# Sheet1.net
KiCad netlist of a schematic drawn in Altium Designer
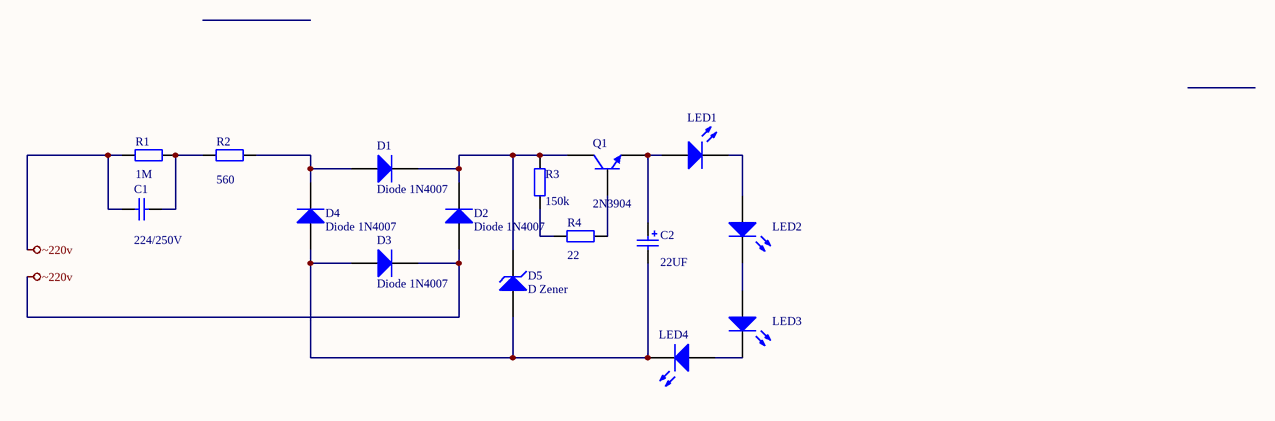
[diagram p0: Sheet1.SchDoc]

(export (version "E")
  (design (tool "Eeschema 10.0.6"))
  (components
    (comp (ref "C1")
      (value "224/250V")
      (footprint "RAD-0.3")
      (description "Capacitor")
      (fields (field (name "PUBLISHER") "Altium Limited"))
      (libsource (lib "Miscellaneous Devices") (part "Cap"))
    )
    (comp (ref "C2")
      (value "22UF")
      (footprint "POLAR0.8")
      (description "Polarized Capacitor (Axial)")
      (fields (field (name "PUBLISHER") "Altium Limited"))
      (libsource (lib "Miscellaneous Devices") (part "Cap Pol2"))
    )
    (comp (ref "D1")
      (value "Diode 1N4007")
      (footprint "DO-41")
      (description "1 Amp General Purpose Rectifier")
      (fields (field (name "PUBLISHER") "Altium Limited"))
      (libsource (lib "Miscellaneous Devices") (part "Diode 1N4007"))
    )
    (comp (ref "D2")
      (value "Diode 1N4007")
      (footprint "DO-41")
      (description "1 Amp General Purpose Rectifier")
      (fields (field (name "PUBLISHER") "Altium Limited"))
      (libsource (lib "Miscellaneous Devices") (part "Diode 1N4007"))
    )
    (comp (ref "D3")
      (value "Diode 1N4007")
      (footprint "DO-41")
      (description "1 Amp General Purpose Rectifier")
      (fields (field (name "PUBLISHER") "Altium Limited"))
      (libsource (lib "Miscellaneous Devices") (part "Diode 1N4007"))
    )
    (comp (ref "D4")
      (value "Diode 1N4007")
      (footprint "DO-41")
      (description "1 Amp General Purpose Rectifier")
      (fields (field (name "PUBLISHER") "Altium Limited"))
      (libsource (lib "Miscellaneous Devices") (part "Diode 1N4007"))
    )
    (comp (ref "D5")
      (value "D Zener")
      (footprint "DIODE-0.7")
      (description "Zener Diode")
      (fields (field (name "PUBLISHER") "Altium Limited"))
      (libsource (lib "Miscellaneous Devices") (part "D Zener"))
    )
    (comp (ref "LED1")
      (value "~")
      (footprint "LED-0")
      (description "Typical INFRARED GaAs LED")
      (fields (field (name "PUBLISHER") "Altium Limited"))
      (libsource (lib "Miscellaneous Devices") (part "LED0"))
    )
    (comp (ref "LED2")
      (value "~")
      (footprint "LED-0")
      (description "Typical INFRARED GaAs LED")
      (fields (field (name "PUBLISHER") "Altium Limited"))
      (libsource (lib "Miscellaneous Devices") (part "LED0"))
    )
    (comp (ref "LED3")
      (value "~")
      (footprint "LED-0")
      (description "Typical INFRARED GaAs LED")
      (fields (field (name "PUBLISHER") "Altium Limited"))
      (libsource (lib "Miscellaneous Devices") (part "LED0"))
    )
    (comp (ref "LED4")
      (value "~")
      (footprint "LED-0")
      (description "Typical INFRARED GaAs LED")
      (fields (field (name "PUBLISHER") "Altium Limited"))
      (libsource (lib "Miscellaneous Devices") (part "LED0"))
    )
    (comp (ref "Q1")
      (value "2N3904")
      (footprint "TO-92A")
      (description "NPN General Purpose Amplifier")
      (fields (field (name "PUBLISHER") "Altium Limited"))
      (libsource (lib "Miscellaneous Devices") (part "2N3904"))
    )
    (comp (ref "R1")
      (value "1M")
      (footprint "AXIAL-0.4")
      (description "Resistor")
      (fields (field (name "PUBLISHER") "Altium Limited"))
      (libsource (lib "") (part "Res2_2"))
    )
    (comp (ref "R2")
      (value "560")
      (footprint "AXIAL-0.4")
      (description "Resistor")
      (fields (field (name "PUBLISHER") "Altium Limited"))
      (libsource (lib "") (part "Res2_2"))
    )
    (comp (ref "R3")
      (value "150k")
      (footprint "AXIAL-0.4")
      (description "Resistor")
      (fields (field (name "PUBLISHER") "Altium Limited"))
      (libsource (lib "") (part "Res2_1"))
    )
    (comp (ref "R4")
      (value "22")
      (footprint "AXIAL-0.4")
      (description "Resistor")
      (fields (field (name "PUBLISHER") "Altium Limited"))
      (libsource (lib "Miscellaneous Devices") (part "Res2"))
    )
  )
  (nets
    (net (code "1") (name "Net-(C1-Pad2)") (class "Default")
      (node (ref "C1") (pin "2") (pinfunction "2_2") (pintype "passive"))
      (node (ref "R1") (pin "2") (pinfunction "2_2") (pintype "passive"))
      (node (ref "R2") (pin "1") (pinfunction "1_1") (pintype "passive"))
    )
    (net (code "2") (name "Net-(D1-A)") (class "Default")
      (node (ref "D1") (pin "1") (pinfunction "A_1") (pintype "passive"))
      (node (ref "D4") (pin "2") (pinfunction "K_2") (pintype "passive"))
      (node (ref "R2") (pin "2") (pinfunction "2_2") (pintype "passive"))
    )
    (net (code "3") (name "Net-(D1-K)") (class "Default")
      (node (ref "D1") (pin "2") (pinfunction "K_2") (pintype "passive"))
      (node (ref "D2") (pin "2") (pinfunction "K_2") (pintype "passive"))
      (node (ref "D5") (pin "2") (pinfunction "K_2") (pintype "passive"))
      (node (ref "Q1") (pin "3") (pinfunction "C_3") (pintype "passive"))
      (node (ref "R3") (pin "2") (pinfunction "2_2") (pintype "passive"))
    )
    (net (code "4") (name "Net-(D3-A)") (class "Default")
      (node (ref "C2") (pin "2") (pinfunction "2_2") (pintype "passive"))
      (node (ref "D3") (pin "1") (pinfunction "A_1") (pintype "passive"))
      (node (ref "D4") (pin "1") (pinfunction "A_1") (pintype "passive"))
      (node (ref "D5") (pin "1") (pinfunction "A_1") (pintype "passive"))
      (node (ref "LED4") (pin "2") (pinfunction "K_2") (pintype "passive"))
    )
    (net (code "5") (name "Net-(LED1-A)") (class "Default")
      (node (ref "C2") (pin "1") (pinfunction "1_1") (pintype "passive"))
      (node (ref "LED1") (pin "1") (pinfunction "A_1") (pintype "passive"))
      (node (ref "Q1") (pin "1") (pinfunction "E_1") (pintype "passive"))
    )
    (net (code "6") (name "Net-(LED1-K)") (class "Default")
      (node (ref "LED1") (pin "2") (pinfunction "K_2") (pintype "passive"))
      (node (ref "LED2") (pin "1") (pinfunction "A_1") (pintype "passive"))
    )
    (net (code "7") (name "Net-(LED2-K)") (class "Default")
      (node (ref "LED2") (pin "2") (pinfunction "K_2") (pintype "passive"))
      (node (ref "LED3") (pin "1") (pinfunction "A_1") (pintype "passive"))
    )
    (net (code "8") (name "Net-(LED3-K)") (class "Default")
      (node (ref "LED3") (pin "2") (pinfunction "K_2") (pintype "passive"))
      (node (ref "LED4") (pin "1") (pinfunction "A_1") (pintype "passive"))
    )
    (net (code "9") (name "Net-(Q1-B)") (class "Default")
      (node (ref "Q1") (pin "2") (pinfunction "B_2") (pintype "passive"))
      (node (ref "R4") (pin "1") (pinfunction "1_1") (pintype "passive"))
    )
    (net (code "10") (name "Net-(R3-Pad1)") (class "Default")
      (node (ref "R3") (pin "1") (pinfunction "1_1") (pintype "passive"))
      (node (ref "R4") (pin "2") (pinfunction "2_2") (pintype "passive"))
    )
    (net (code "11") (name "~220v") (class "Default")
      (node (ref "C1") (pin "1") (pinfunction "1_1") (pintype "passive"))
      (node (ref "D2") (pin "1") (pinfunction "A_1") (pintype "passive"))
      (node (ref "D3") (pin "2") (pinfunction "K_2") (pintype "passive"))
      (node (ref "R1") (pin "1") (pinfunction "1_1") (pintype "passive"))
    )
  )
)
